# breadboarder_minimizing.net
KiCad netlist of a schematic drawn in EAGLE
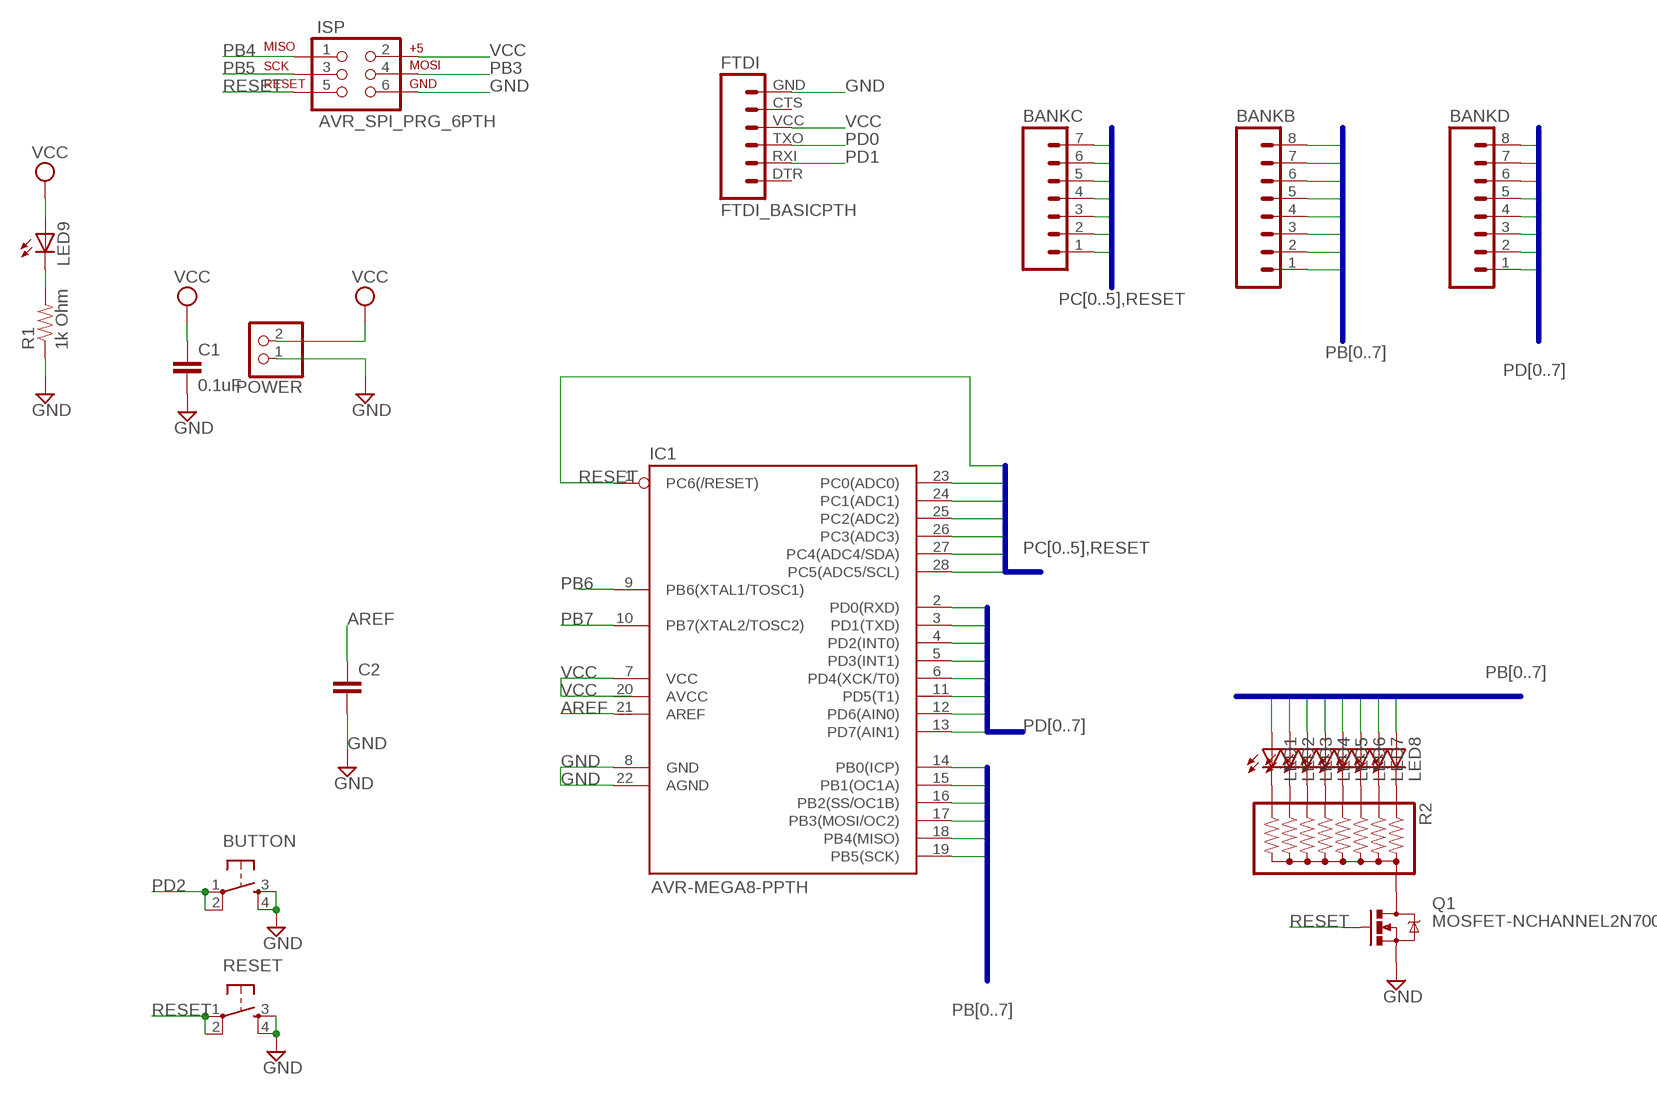
[diagram p0: schematic, sheet 1]

(export (version "E")
  (design (tool "Eeschema 10.0.6"))
  (components
    (comp (ref "BANKB")
      (value "M08LONGPADS")
      (footprint "eagle-import:1X08_LONGPADS")
      (libsource (lib "eagle-import") (part "M08LONGPADS"))
    )
    (comp (ref "BANKC")
      (value "M07LONGPADS")
      (footprint "eagle-import:1X07_LONGPADS")
      (libsource (lib "eagle-import") (part "M07LONGPADS"))
    )
    (comp (ref "BANKD")
      (value "M08LONGPADS")
      (footprint "eagle-import:1X08_LONGPADS")
      (libsource (lib "eagle-import") (part "M08LONGPADS"))
    )
    (comp (ref "BUTTON")
      (value "TAC_SWITCHPTH")
      (footprint "eagle-import:TACTILE-PTH")
      (libsource (lib "eagle-import") (part "TAC_SWITCHPTH"))
    )
    (comp (ref "C1")
      (value "0.1uF")
      (footprint "eagle-import:CAP-PTH-SMALL-KIT")
      (libsource (lib "eagle-import") (part "CAPKIT"))
    )
    (comp (ref "C2")
      (value "CAPKIT")
      (footprint "eagle-import:CAP-PTH-SMALL-KIT")
      (libsource (lib "eagle-import") (part "CAPKIT"))
    )
    (comp (ref "FTDI")
      (value "FTDI_BASICPTH")
      (footprint "eagle-import:FTDI_BASIC")
      (libsource (lib "eagle-import") (part "FTDI_BASICPTH"))
    )
    (comp (ref "IC1")
      (value "AVR-MEGA8-PPTH")
      (footprint "eagle-import:DIL28-3")
      (libsource (lib "eagle-import") (part "AVR-MEGA8-PPTH"))
    )
    (comp (ref "ISP")
      (value "AVR_SPI_PRG_6PTH")
      (footprint "eagle-import:2X3")
      (libsource (lib "eagle-import") (part "AVR_SPI_PRG_6PTH"))
    )
    (comp (ref "LED1")
      (value "LED3MM")
      (footprint "eagle-import:LED3MM")
      (libsource (lib "eagle-import") (part "LED3MM"))
    )
    (comp (ref "LED2")
      (value "LED3MM")
      (footprint "eagle-import:LED3MM")
      (libsource (lib "eagle-import") (part "LED3MM"))
    )
    (comp (ref "LED3")
      (value "LED3MM")
      (footprint "eagle-import:LED3MM")
      (libsource (lib "eagle-import") (part "LED3MM"))
    )
    (comp (ref "LED4")
      (value "LED3MM")
      (footprint "eagle-import:LED3MM")
      (libsource (lib "eagle-import") (part "LED3MM"))
    )
    (comp (ref "LED5")
      (value "LED3MM")
      (footprint "eagle-import:LED3MM")
      (libsource (lib "eagle-import") (part "LED3MM"))
    )
    (comp (ref "LED6")
      (value "LED3MM")
      (footprint "eagle-import:LED3MM")
      (libsource (lib "eagle-import") (part "LED3MM"))
    )
    (comp (ref "LED7")
      (value "LED3MM")
      (footprint "eagle-import:LED3MM")
      (libsource (lib "eagle-import") (part "LED3MM"))
    )
    (comp (ref "LED8")
      (value "LED3MM")
      (footprint "eagle-import:LED3MM")
      (libsource (lib "eagle-import") (part "LED3MM"))
    )
    (comp (ref "LED9")
      (value "LED3MM")
      (footprint "eagle-import:LED3MM")
      (libsource (lib "eagle-import") (part "LED3MM"))
    )
    (comp (ref "POWER")
      (value "PINHD-1X2")
      (footprint "eagle-import:1X02")
      (libsource (lib "eagle-import") (part "PINHD-1X2"))
    )
    (comp (ref "Q1")
      (value "MOSFET-NCHANNEL2N7000")
      (footprint "eagle-import:TO-92")
      (libsource (lib "eagle-import") (part "MOSFET-NCHANNEL2N7000"))
    )
    (comp (ref "R1")
      (value "1k Ohm")
      (footprint "eagle-import:AXIAL-0.3")
      (libsource (lib "eagle-import") (part "RESISTORAXIAL-0.3"))
    )
    (comp (ref "R2")
      (value "RPACK-BUSSED-8SIP-PTH-8-LP")
      (footprint "eagle-import:RPACK-SIP-PTH-8-LP")
      (libsource (lib "eagle-import") (part "RPACK-BUSSED-8SIP-PTH-8-LP"))
    )
    (comp (ref "RESET")
      (value "TAC_SWITCHPTH")
      (footprint "eagle-import:TACTILE-PTH")
      (libsource (lib "eagle-import") (part "TAC_SWITCHPTH"))
    )
  )
  (nets
    (net (code "1") (name "/AREF") (class "Default")
      (node (ref "C2") (pin "1") (pinfunction "1_1") (pintype "passive"))
      (node (ref "IC1") (pin "21") (pinfunction "AREF_21") (pintype "bidirectional"))
    )
    (net (code "2") (name "/PB0") (class "Default")
      (node (ref "BANKB") (pin "8") (pinfunction "8_8") (pintype "passive"))
      (node (ref "IC1") (pin "14") (pinfunction "PB0(ICP)_14") (pintype "bidirectional"))
      (node (ref "LED1") (pin "A") (pinfunction "A_A") (pintype "passive"))
    )
    (net (code "3") (name "/PB1") (class "Default")
      (node (ref "BANKB") (pin "7") (pinfunction "7_7") (pintype "passive"))
      (node (ref "IC1") (pin "15") (pinfunction "PB1(OC1A)_15") (pintype "bidirectional"))
      (node (ref "LED2") (pin "A") (pinfunction "A_A") (pintype "passive"))
    )
    (net (code "4") (name "/PB2") (class "Default")
      (node (ref "BANKB") (pin "6") (pinfunction "6_6") (pintype "passive"))
      (node (ref "IC1") (pin "16") (pinfunction "PB2(SS/OC1B)_16") (pintype "bidirectional"))
      (node (ref "LED3") (pin "A") (pinfunction "A_A") (pintype "passive"))
    )
    (net (code "5") (name "/PB3") (class "Default")
      (node (ref "BANKB") (pin "5") (pinfunction "5_5") (pintype "passive"))
      (node (ref "IC1") (pin "17") (pinfunction "PB3(MOSI/OC2)_17") (pintype "bidirectional"))
      (node (ref "ISP") (pin "4") (pinfunction "4_4") (pintype "passive"))
      (node (ref "LED4") (pin "A") (pinfunction "A_A") (pintype "passive"))
    )
    (net (code "6") (name "/PB4") (class "Default")
      (node (ref "BANKB") (pin "4") (pinfunction "4_4") (pintype "passive"))
      (node (ref "IC1") (pin "18") (pinfunction "PB4(MISO)_18") (pintype "bidirectional"))
      (node (ref "ISP") (pin "1") (pinfunction "1_1") (pintype "passive"))
      (node (ref "LED5") (pin "A") (pinfunction "A_A") (pintype "passive"))
    )
    (net (code "7") (name "/PB5") (class "Default")
      (node (ref "BANKB") (pin "3") (pinfunction "3_3") (pintype "passive"))
      (node (ref "IC1") (pin "19") (pinfunction "PB5(SCK)_19") (pintype "bidirectional"))
      (node (ref "ISP") (pin "3") (pinfunction "3_3") (pintype "passive"))
      (node (ref "LED6") (pin "A") (pinfunction "A_A") (pintype "passive"))
    )
    (net (code "8") (name "/PB6") (class "Default")
      (node (ref "BANKB") (pin "2") (pinfunction "2_2") (pintype "passive"))
      (node (ref "IC1") (pin "9") (pinfunction "PB6(XTAL1/TOSC1)_9") (pintype "bidirectional"))
      (node (ref "LED7") (pin "A") (pinfunction "A_A") (pintype "passive"))
    )
    (net (code "9") (name "/PB7") (class "Default")
      (node (ref "BANKB") (pin "1") (pinfunction "1_1") (pintype "passive"))
      (node (ref "IC1") (pin "10") (pinfunction "PB7(XTAL2/TOSC2)_10") (pintype "bidirectional"))
      (node (ref "LED8") (pin "A") (pinfunction "A_A") (pintype "passive"))
    )
    (net (code "11") (name "/PC0") (class "Default")
      (node (ref "BANKC") (pin "7") (pinfunction "7_7") (pintype "passive"))
      (node (ref "IC1") (pin "23") (pinfunction "PC0(ADC0)_23") (pintype "bidirectional"))
    )
    (net (code "12") (name "/PC1") (class "Default")
      (node (ref "BANKC") (pin "6") (pinfunction "6_6") (pintype "passive"))
      (node (ref "IC1") (pin "24") (pinfunction "PC1(ADC1)_24") (pintype "bidirectional"))
    )
    (net (code "13") (name "/PC2") (class "Default")
      (node (ref "BANKC") (pin "5") (pinfunction "5_5") (pintype "passive"))
      (node (ref "IC1") (pin "25") (pinfunction "PC2(ADC2)_25") (pintype "bidirectional"))
    )
    (net (code "14") (name "/PC3") (class "Default")
      (node (ref "BANKC") (pin "4") (pinfunction "4_4") (pintype "passive"))
      (node (ref "IC1") (pin "26") (pinfunction "PC3(ADC3)_26") (pintype "bidirectional"))
    )
    (net (code "15") (name "/PC4") (class "Default")
      (node (ref "BANKC") (pin "3") (pinfunction "3_3") (pintype "passive"))
      (node (ref "IC1") (pin "27") (pinfunction "PC4(ADC4/SDA)_27") (pintype "bidirectional"))
    )
    (net (code "16") (name "/PC5") (class "Default")
      (node (ref "BANKC") (pin "2") (pinfunction "2_2") (pintype "passive"))
      (node (ref "IC1") (pin "28") (pinfunction "PC5(ADC5/SCL)_28") (pintype "bidirectional"))
    )
    (net (code "17") (name "/PD0") (class "Default")
      (node (ref "BANKD") (pin "8") (pinfunction "8_8") (pintype "passive"))
      (node (ref "FTDI") (pin "TXO") (pinfunction "3_TXO") (pintype "passive"))
      (node (ref "IC1") (pin "2") (pinfunction "PD0(RXD)_2") (pintype "bidirectional"))
    )
    (net (code "18") (name "/PD1") (class "Default")
      (node (ref "BANKD") (pin "7") (pinfunction "7_7") (pintype "passive"))
      (node (ref "FTDI") (pin "RXI") (pinfunction "2_RXI") (pintype "passive"))
      (node (ref "IC1") (pin "3") (pinfunction "PD1(TXD)_3") (pintype "bidirectional"))
    )
    (net (code "19") (name "/PD2") (class "Default")
      (node (ref "BANKD") (pin "6") (pinfunction "6_6") (pintype "passive"))
      (node (ref "BUTTON") (pin "1") (pinfunction "1_1") (pintype "passive"))
      (node (ref "BUTTON") (pin "2") (pinfunction "2_2") (pintype "passive"))
      (node (ref "IC1") (pin "4") (pinfunction "PD2(INT0)_4") (pintype "bidirectional"))
    )
    (net (code "20") (name "/PD3") (class "Default")
      (node (ref "BANKD") (pin "5") (pinfunction "5_5") (pintype "passive"))
      (node (ref "IC1") (pin "5") (pinfunction "PD3(INT1)_5") (pintype "bidirectional"))
    )
    (net (code "21") (name "/PD4") (class "Default")
      (node (ref "BANKD") (pin "4") (pinfunction "4_4") (pintype "passive"))
      (node (ref "IC1") (pin "6") (pinfunction "PD4(XCK/T0)_6") (pintype "bidirectional"))
    )
    (net (code "22") (name "/PD5") (class "Default")
      (node (ref "BANKD") (pin "3") (pinfunction "3_3") (pintype "passive"))
      (node (ref "IC1") (pin "11") (pinfunction "PD5(T1)_11") (pintype "bidirectional"))
    )
    (net (code "23") (name "/PD6") (class "Default")
      (node (ref "BANKD") (pin "2") (pinfunction "2_2") (pintype "passive"))
      (node (ref "IC1") (pin "12") (pinfunction "PD6(AIN0)_12") (pintype "bidirectional"))
    )
    (net (code "24") (name "/PD7") (class "Default")
      (node (ref "BANKD") (pin "1") (pinfunction "1_1") (pintype "passive"))
      (node (ref "IC1") (pin "13") (pinfunction "PD7(AIN1)_13") (pintype "bidirectional"))
    )
    (net (code "26") (name "/RESET") (class "Default")
      (node (ref "BANKC") (pin "1") (pinfunction "1_1") (pintype "passive"))
      (node (ref "IC1") (pin "1") (pinfunction "PC6(/RESET)_1") (pintype "bidirectional"))
      (node (ref "ISP") (pin "5") (pinfunction "5_5") (pintype "passive"))
      (node (ref "Q1") (pin "2") (pinfunction "G_2") (pintype "passive"))
      (node (ref "RESET") (pin "1") (pinfunction "1_1") (pintype "passive"))
      (node (ref "RESET") (pin "2") (pinfunction "2_2") (pintype "passive"))
    )
    (net (code "28") (name "GND") (class "Default")
      (node (ref "BUTTON") (pin "3") (pinfunction "3_3") (pintype "passive"))
      (node (ref "BUTTON") (pin "4") (pinfunction "4_4") (pintype "passive"))
      (node (ref "C1") (pin "2") (pinfunction "2_2") (pintype "passive"))
      (node (ref "C2") (pin "2") (pinfunction "2_2") (pintype "passive"))
      (node (ref "FTDI") (pin "GND") (pinfunction "6_GND") (pintype "passive"))
      (node (ref "IC1") (pin "22") (pinfunction "AGND_22") (pintype "bidirectional"))
      (node (ref "IC1") (pin "8") (pinfunction "GND_8") (pintype "bidirectional"))
      (node (ref "ISP") (pin "6") (pinfunction "6_6") (pintype "passive"))
      (node (ref "POWER") (pin "1") (pinfunction "1_1") (pintype "passive"))
      (node (ref "Q1") (pin "1") (pinfunction "S_1") (pintype "passive"))
      (node (ref "R1") (pin "P$1") (pinfunction "1_P$1") (pintype "passive"))
      (node (ref "RESET") (pin "3") (pinfunction "3_3") (pintype "passive"))
      (node (ref "RESET") (pin "4") (pinfunction "4_4") (pintype "passive"))
    )
    (net (code "29") (name "Net-(LED1-C)") (class "Default")
      (node (ref "LED1") (pin "K") (pinfunction "C_K") (pintype "passive"))
      (node (ref "R2") (pin "P$9") (pinfunction "9_P$9") (pintype "passive"))
    )
    (net (code "30") (name "Net-(LED2-C)") (class "Default")
      (node (ref "LED2") (pin "K") (pinfunction "C_K") (pintype "passive"))
      (node (ref "R2") (pin "P$8") (pinfunction "8_P$8") (pintype "passive"))
    )
    (net (code "31") (name "Net-(LED3-C)") (class "Default")
      (node (ref "LED3") (pin "K") (pinfunction "C_K") (pintype "passive"))
      (node (ref "R2") (pin "P$7") (pinfunction "7_P$7") (pintype "passive"))
    )
    (net (code "32") (name "Net-(LED4-C)") (class "Default")
      (node (ref "LED4") (pin "K") (pinfunction "C_K") (pintype "passive"))
      (node (ref "R2") (pin "P$6") (pinfunction "6_P$6") (pintype "passive"))
    )
    (net (code "33") (name "Net-(LED5-C)") (class "Default")
      (node (ref "LED5") (pin "K") (pinfunction "C_K") (pintype "passive"))
      (node (ref "R2") (pin "P$5") (pinfunction "5_P$5") (pintype "passive"))
    )
    (net (code "34") (name "Net-(LED6-C)") (class "Default")
      (node (ref "LED6") (pin "K") (pinfunction "C_K") (pintype "passive"))
      (node (ref "R2") (pin "P$4") (pinfunction "4_P$4") (pintype "passive"))
    )
    (net (code "35") (name "Net-(LED7-C)") (class "Default")
      (node (ref "LED7") (pin "K") (pinfunction "C_K") (pintype "passive"))
      (node (ref "R2") (pin "P$3") (pinfunction "3_P$3") (pintype "passive"))
    )
    (net (code "36") (name "Net-(LED8-C)") (class "Default")
      (node (ref "LED8") (pin "K") (pinfunction "C_K") (pintype "passive"))
      (node (ref "R2") (pin "P$2") (pinfunction "2_P$2") (pintype "passive"))
    )
    (net (code "37") (name "Net-(LED9-C)") (class "Default")
      (node (ref "LED9") (pin "K") (pinfunction "C_K") (pintype "passive"))
      (node (ref "R1") (pin "P$2") (pinfunction "2_P$2") (pintype "passive"))
    )
    (net (code "38") (name "Net-(Q1-D)") (class "Default")
      (node (ref "Q1") (pin "3") (pinfunction "D_3") (pintype "passive"))
      (node (ref "R2") (pin "P$1") (pinfunction "1_P$1") (pintype "passive"))
    )
    (net (code "39") (name "VCC") (class "Default")
      (node (ref "C1") (pin "1") (pinfunction "1_1") (pintype "passive"))
      (node (ref "FTDI") (pin "VCC") (pinfunction "4_VCC") (pintype "passive"))
      (node (ref "IC1") (pin "7") (pinfunction "VCC_7") (pintype "bidirectional"))
      (node (ref "ISP") (pin "2") (pinfunction "2_2") (pintype "passive"))
      (node (ref "LED9") (pin "A") (pinfunction "A_A") (pintype "passive"))
      (node (ref "POWER") (pin "2") (pinfunction "2_2") (pintype "passive"))
    )
    (net (code "40") (name "unconnected-(FTDI-1-PadDTR)") (class "Default")
      (node (ref "FTDI") (pin "DTR") (pinfunction "1_DTR") (pintype "passive"))
    )
    (net (code "41") (name "unconnected-(FTDI-5-PadCTS)") (class "Default")
      (node (ref "FTDI") (pin "CTS") (pinfunction "5_CTS") (pintype "passive"))
    )
    (net (code "42") (name "unconnected-(IC1-AVCC-Pad20)") (class "Default")
      (node (ref "IC1") (pin "20") (pinfunction "AVCC_20") (pintype "bidirectional"))
    )
  )
)
